# IMU.net
KiCad netlist of a schematic drawn in Altium Designer
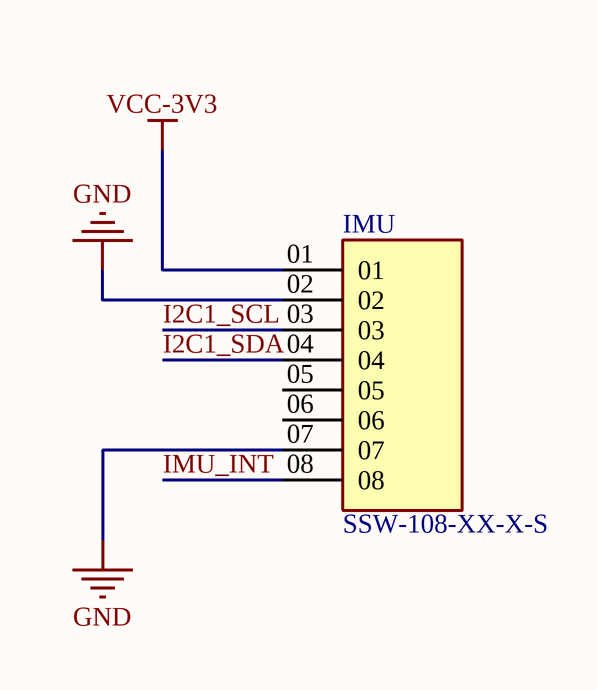
[diagram p0: IMU.SchDoc]

(export (version "E")
  (design (tool "Eeschema 10.0.6"))
  (components
    (comp (ref "IMU")
      (value "SSW-108-XX-X-S")
      (footprint "SAMTEC_SSW-108-XX-X-S")
      (description "8 Position Receptacle Connector 0.100 (2.54mm) Through Hole, Right Angle Gold")
      (fields (field (name "MF") "Samtec") (field (name "MP") "SSW-108-23-G-S"))
      (libsource (lib "SSW-108-XX-X-S") (part "SSW-108-XX-X-S"))
    )
  )
  (nets
    (net (code "1") (name "/I2C1_SCL") (class "Default")
      (node (ref "IMU") (pin "03") (pinfunction "03_03") (pintype "passive"))
    )
    (net (code "2") (name "/I2C1_SDA") (class "Default")
      (node (ref "IMU") (pin "04") (pinfunction "04_04") (pintype "passive"))
    )
    (net (code "3") (name "/IMU_INT") (class "Default")
      (node (ref "IMU") (pin "08") (pinfunction "08_08") (pintype "passive"))
    )
    (net (code "4") (name "GND") (class "Default")
      (node (ref "IMU") (pin "02") (pinfunction "02_02") (pintype "passive"))
      (node (ref "IMU") (pin "07") (pinfunction "07_07") (pintype "passive"))
    )
    (net (code "5") (name "VCC-3V3") (class "Default")
      (node (ref "IMU") (pin "01") (pinfunction "01_01") (pintype "passive"))
    )
    (net (code "6") (name "unconnected-(IMU-Pad05)") (class "Default")
      (node (ref "IMU") (pin "05") (pinfunction "05_05") (pintype "passive"))
    )
    (net (code "7") (name "unconnected-(IMU-Pad06)") (class "Default")
      (node (ref "IMU") (pin "06") (pinfunction "06_06") (pintype "passive"))
    )
  )
)
